# TFT_Touch.net
KiCad netlist of a schematic drawn in EAGLE
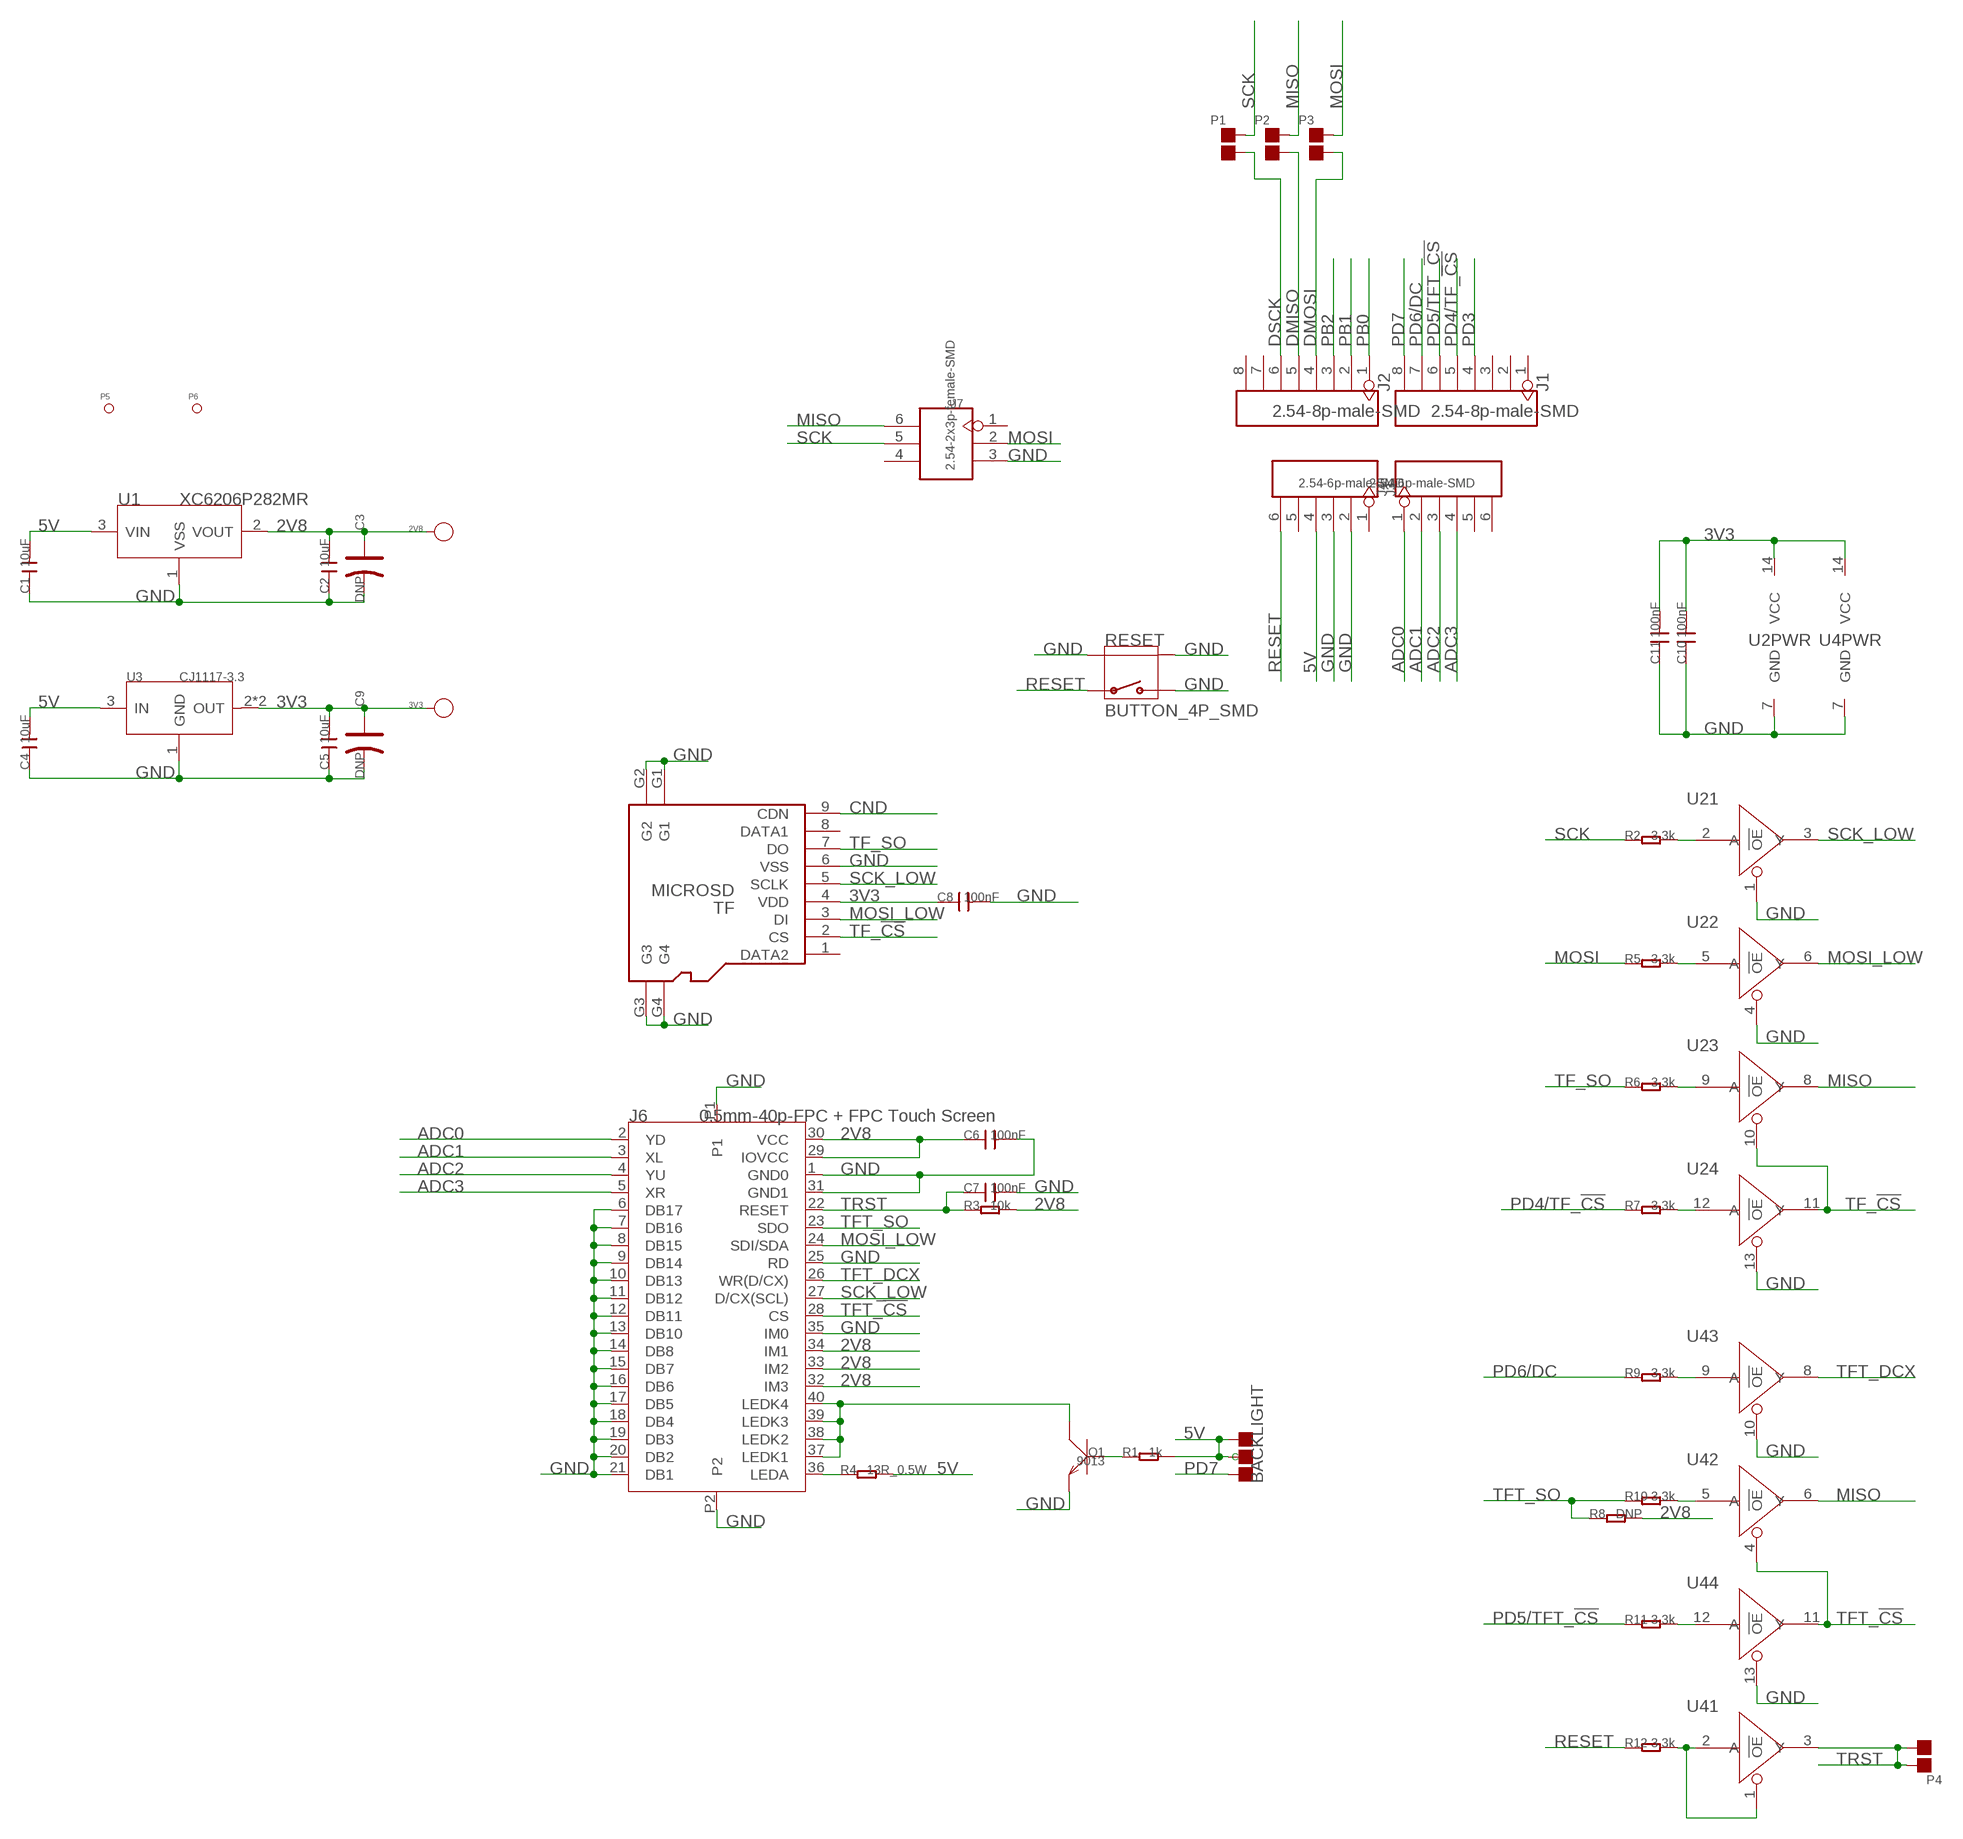
[diagram p0: schematic, sheet 1]

(export (version "E")
  (design (tool "Eeschema 10.0.6"))
  (components
    (comp (ref "2V8")
      (value "PAD-TEST-POINT-CIRCLE'4545'")
      (footprint "eagle-import:TP_4545")
      (fields (field (name "PARTNO") "DNP"))
      (libsource (lib "eagle-import") (part "PAD-TEST-POINT-CIRCLE'4545'"))
    )
    (comp (ref "3V3")
      (value "PAD-TEST-POINT-CIRCLE'4545'")
      (footprint "eagle-import:TP_4545")
      (fields (field (name "PARTNO") "DNP"))
      (libsource (lib "eagle-import") (part "PAD-TEST-POINT-CIRCLE'4545'"))
    )
    (comp (ref "BACKLIGHT")
      (value "DNP")
      (footprint "eagle-import:3P-SMD-4.1X1.5")
      (libsource (lib "eagle-import") (part "PAD-JUMPER-3P-4040"))
    )
    (comp (ref "C1")
      (value "10uF")
      (footprint "eagle-import:C0805")
      (libsource (lib "eagle-import") (part "C-0805"))
    )
    (comp (ref "C2")
      (value "10uF")
      (footprint "eagle-import:C0805")
      (libsource (lib "eagle-import") (part "C-0805"))
    )
    (comp (ref "C3")
      (value "DNP")
      (footprint "eagle-import:AVX-A")
      (libsource (lib "eagle-import") (part "CAP-AVX-A"))
    )
    (comp (ref "C4")
      (value "10uF")
      (footprint "eagle-import:C0805")
      (libsource (lib "eagle-import") (part "C-0805"))
    )
    (comp (ref "C5")
      (value "10uF")
      (footprint "eagle-import:C0805")
      (libsource (lib "eagle-import") (part "C-0805"))
    )
    (comp (ref "C6")
      (value "100nF")
      (footprint "eagle-import:0603@1")
      (libsource (lib "eagle-import") (part "006-C3540"))
    )
    (comp (ref "C7")
      (value "100nF")
      (footprint "eagle-import:0603@1")
      (libsource (lib "eagle-import") (part "006-C3540"))
    )
    (comp (ref "C8")
      (value "100nF")
      (footprint "eagle-import:0603@1")
      (libsource (lib "eagle-import") (part "006-C3540"))
    )
    (comp (ref "C9")
      (value "DNP")
      (footprint "eagle-import:AVX-A")
      (libsource (lib "eagle-import") (part "CAP-AVX-A"))
    )
    (comp (ref "C10")
      (value "100nF")
      (footprint "eagle-import:0603@1")
      (libsource (lib "eagle-import") (part "006-C3540"))
    )
    (comp (ref "C11")
      (value "100nF")
      (footprint "eagle-import:0603@1")
      (libsource (lib "eagle-import") (part "006-C3540"))
    )
    (comp (ref "J1")
      (value "2.54-8p-male-SMD")
      (footprint "eagle-import:8P-2.54-SMD")
      (libsource (lib "eagle-import") (part "HEADER-8P-2.54-SMD"))
    )
    (comp (ref "J2")
      (value "2.54-8p-male-SMD")
      (footprint "eagle-import:8P-2.54-SMD")
      (libsource (lib "eagle-import") (part "HEADER-8P-2.54-SMD"))
    )
    (comp (ref "J3")
      (value "2.54-6p-male-SMD")
      (footprint "eagle-import:6P-2.54-SMD")
      (libsource (lib "eagle-import") (part "HEADER-6P-SMD"))
    )
    (comp (ref "J4")
      (value "2.54-6p-male-SMD")
      (footprint "eagle-import:6P-2.54-SMD")
      (libsource (lib "eagle-import") (part "HEADER-6P-SMD"))
    )
    (comp (ref "J6")
      (value "0.5mm-40p-FPC + FPC Touch Screen")
      (footprint "eagle-import:2.8TFT_FFC")
      (libsource (lib "eagle-import") (part "2.8TFT_FPC"))
    )
    (comp (ref "J7")
      (value "2.54-2x3p-female-SMD")
      (footprint "eagle-import:2X3P-2.54-SMD")
      (libsource (lib "eagle-import") (part "HEADER-2X3P-SMD"))
    )
    (comp (ref "P1")
      (value "PAD-JUMPER-2P")
      (footprint "eagle-import:2P-SMD-1.78X1.27")
      (fields (field (name "PARTNO") "DNP"))
      (libsource (lib "eagle-import") (part "PAD-JUMPER-2P"))
    )
    (comp (ref "P2")
      (value "PAD-JUMPER-2P")
      (footprint "eagle-import:2P-SMD-1.78X1.27")
      (fields (field (name "PARTNO") "DNP"))
      (libsource (lib "eagle-import") (part "PAD-JUMPER-2P"))
    )
    (comp (ref "P3")
      (value "PAD-JUMPER-2P")
      (footprint "eagle-import:2P-SMD-1.78X1.27")
      (fields (field (name "PARTNO") "DNP"))
      (libsource (lib "eagle-import") (part "PAD-JUMPER-2P"))
    )
    (comp (ref "P4")
      (value "PAD-JUMPER-2P")
      (footprint "eagle-import:2P-SMD-1.78X1.27")
      (fields (field (name "PARTNO") "DNP"))
      (libsource (lib "eagle-import") (part "PAD-JUMPER-2P"))
    )
    (comp (ref "P5")
      (value "PAD-MARK")
      (footprint "eagle-import:ROUND-MARK-1.0")
      (fields (field (name "PARTNO") "DNP"))
      (libsource (lib "eagle-import") (part "PAD-MARK"))
    )
    (comp (ref "P6")
      (value "PAD-MARK")
      (footprint "eagle-import:ROUND-MARK-1.0")
      (fields (field (name "PARTNO") "DNP"))
      (libsource (lib "eagle-import") (part "PAD-MARK"))
    )
    (comp (ref "Q1")
      (value "9013")
      (footprint "eagle-import:SOT23")
      (libsource (lib "eagle-import") (part "TRANSISTOR-NPN-SOT23"))
    )
    (comp (ref "R1")
      (value "1k")
      (footprint "eagle-import:R0603")
      (libsource (lib "eagle-import") (part "R-0603"))
    )
    (comp (ref "R2")
      (value "3.3k")
      (footprint "eagle-import:R0603")
      (libsource (lib "eagle-import") (part "R-0603"))
    )
    (comp (ref "R3")
      (value "10k")
      (footprint "eagle-import:R0603")
      (libsource (lib "eagle-import") (part "R-0603"))
    )
    (comp (ref "R4")
      (value "13R_0.5W")
      (footprint "eagle-import:R1206")
      (libsource (lib "eagle-import") (part "R-1206"))
    )
    (comp (ref "R5")
      (value "3.3k")
      (footprint "eagle-import:R0603")
      (libsource (lib "eagle-import") (part "R-0603"))
    )
    (comp (ref "R6")
      (value "3.3k")
      (footprint "eagle-import:R0603")
      (libsource (lib "eagle-import") (part "R-0603"))
    )
    (comp (ref "R7")
      (value "3.3k")
      (footprint "eagle-import:R0603")
      (libsource (lib "eagle-import") (part "R-0603"))
    )
    (comp (ref "R8")
      (value "DNP")
      (footprint "eagle-import:R0603")
      (libsource (lib "eagle-import") (part "R-0603"))
    )
    (comp (ref "R9")
      (value "3.3k")
      (footprint "eagle-import:R0603")
      (libsource (lib "eagle-import") (part "R-0603"))
    )
    (comp (ref "R10")
      (value "3.3k")
      (footprint "eagle-import:R0603")
      (libsource (lib "eagle-import") (part "R-0603"))
    )
    (comp (ref "R11")
      (value "3.3k")
      (footprint "eagle-import:R0603")
      (libsource (lib "eagle-import") (part "R-0603"))
    )
    (comp (ref "R12")
      (value "3.3k")
      (footprint "eagle-import:R0603")
      (libsource (lib "eagle-import") (part "R-0603"))
    )
    (comp (ref "RESET")
      (value "BUTTON_4P_SMD")
      (footprint "eagle-import:4P-SMD-7X3.5X3.5")
      (libsource (lib "eagle-import") (part "BUTTON_4P_SMD"))
    )
    (comp (ref "TF")
      (value "MICROSD")
      (footprint "eagle-import:MICROSD")
      (libsource (lib "eagle-import") (part "MICROSD"))
    )
    (comp (ref "U1")
      (value "XC6206P282MR")
      (footprint "eagle-import:SOT23")
      (libsource (lib "eagle-import") (part "XC6206MR"))
    )
    (comp (ref "U2")
      (value "74VHC125PW")
      (footprint "eagle-import:TSSOP14")
      (libsource (lib "eagle-import") (part "74V125PWHC"))
    )
    (comp (ref "U3")
      (value "CJ1117-3.3")
      (footprint "eagle-import:SOT-223")
      (libsource (lib "eagle-import") (part "LD1117S"))
    )
    (comp (ref "U4")
      (value "74VHC125PW")
      (footprint "eagle-import:TSSOP14")
      (libsource (lib "eagle-import") (part "74V125PWHC"))
    )
  )
  (nets
    (net (code "1") (name "/2V8") (class "Default")
      (node (ref "2V8") (pin "T") (pinfunction "T_T") (pintype "bidirectional"))
      (node (ref "C2") (pin "2") (pinfunction "2_2") (pintype "passive"))
      (node (ref "C3") (pin "+") (pinfunction "+_+") (pintype "passive"))
      (node (ref "C6") (pin "1") (pinfunction "1_1") (pintype "passive"))
      (node (ref "J6") (pin "29") (pinfunction "IOVCC_29") (pintype "bidirectional"))
      (node (ref "J6") (pin "30") (pinfunction "VCC_30") (pintype "bidirectional"))
      (node (ref "J6") (pin "32") (pinfunction "IM3_32") (pintype "bidirectional"))
      (node (ref "J6") (pin "33") (pinfunction "IM2_33") (pintype "bidirectional"))
      (node (ref "J6") (pin "34") (pinfunction "IM1_34") (pintype "bidirectional"))
      (node (ref "R3") (pin "2") (pinfunction "2_2") (pintype "passive"))
      (node (ref "R8") (pin "2") (pinfunction "2_2") (pintype "passive"))
      (node (ref "U1") (pin "2") (pinfunction "VOUT_2") (pintype "output"))
    )
    (net (code "2") (name "/3V3") (class "Default")
      (node (ref "3V3") (pin "T") (pinfunction "T_T") (pintype "bidirectional"))
      (node (ref "C10") (pin "2") (pinfunction "2_2") (pintype "passive"))
      (node (ref "C11") (pin "2") (pinfunction "2_2") (pintype "passive"))
      (node (ref "C5") (pin "2") (pinfunction "2_2") (pintype "passive"))
      (node (ref "C8") (pin "1") (pinfunction "1_1") (pintype "passive"))
      (node (ref "C9") (pin "+") (pinfunction "+_+") (pintype "passive"))
      (node (ref "TF") (pin "4") (pinfunction "VDD_4") (pintype "bidirectional"))
      (node (ref "U2") (pin "14") (pinfunction "VCC_14") (pintype "power_in"))
      (node (ref "U3") (pin "2") (pinfunction "OUT_2") (pintype "bidirectional"))
      (node (ref "U3") (pin "TER") (pinfunction "OUT_TER") (pintype "bidirectional"))
      (node (ref "U4") (pin "14") (pinfunction "VCC_14") (pintype "power_in"))
    )
    (net (code "3") (name "/5V") (class "Default")
      (node (ref "BACKLIGHT") (pin "00") (pinfunction "L_00") (pintype "bidirectional"))
      (node (ref "BACKLIGHT") (pin "MM") (pinfunction "C_MM") (pintype "bidirectional"))
      (node (ref "C1") (pin "2") (pinfunction "2_2") (pintype "passive"))
      (node (ref "C4") (pin "2") (pinfunction "2_2") (pintype "passive"))
      (node (ref "J4") (pin "4") (pinfunction "4_4") (pintype "bidirectional"))
      (node (ref "R1") (pin "2") (pinfunction "2_2") (pintype "passive"))
      (node (ref "R4") (pin "2") (pinfunction "2_2") (pintype "passive"))
      (node (ref "U1") (pin "3") (pinfunction "VIN_3") (pintype "input"))
      (node (ref "U3") (pin "3") (pinfunction "IN_3") (pintype "bidirectional"))
    )
    (net (code "4") (name "/ADC0") (class "Default")
      (node (ref "J3") (pin "1") (pinfunction "1_1") (pintype "bidirectional"))
      (node (ref "J6") (pin "2") (pinfunction "YD_2") (pintype "bidirectional"))
    )
    (net (code "5") (name "/ADC1") (class "Default")
      (node (ref "J3") (pin "2") (pinfunction "2_2") (pintype "bidirectional"))
      (node (ref "J6") (pin "3") (pinfunction "XL_3") (pintype "bidirectional"))
    )
    (net (code "6") (name "/ADC2") (class "Default")
      (node (ref "J3") (pin "3") (pinfunction "3_3") (pintype "bidirectional"))
      (node (ref "J6") (pin "4") (pinfunction "YU_4") (pintype "bidirectional"))
    )
    (net (code "7") (name "/ADC3") (class "Default")
      (node (ref "J3") (pin "4") (pinfunction "4_4") (pintype "bidirectional"))
      (node (ref "J6") (pin "5") (pinfunction "XR_5") (pintype "bidirectional"))
    )
    (net (code "8") (name "/CND") (class "Default")
      (node (ref "TF") (pin "9") (pinfunction "CDN_9") (pintype "bidirectional"))
    )
    (net (code "9") (name "/DMISO") (class "Default")
      (node (ref "J2") (pin "5") (pinfunction "5_5") (pintype "bidirectional"))
      (node (ref "P2") (pin "1") (pinfunction "1_1") (pintype "bidirectional"))
    )
    (net (code "10") (name "/DMOSI") (class "Default")
      (node (ref "J2") (pin "4") (pinfunction "4_4") (pintype "bidirectional"))
      (node (ref "P3") (pin "1") (pinfunction "1_1") (pintype "bidirectional"))
    )
    (net (code "11") (name "/DSCK") (class "Default")
      (node (ref "J2") (pin "6") (pinfunction "6_6") (pintype "bidirectional"))
      (node (ref "P1") (pin "1") (pinfunction "1_1") (pintype "bidirectional"))
    )
    (net (code "12") (name "/GND") (class "Default")
      (node (ref "C1") (pin "1") (pinfunction "1_1") (pintype "passive"))
      (node (ref "C10") (pin "1") (pinfunction "1_1") (pintype "passive"))
      (node (ref "C11") (pin "1") (pinfunction "1_1") (pintype "passive"))
      (node (ref "C2") (pin "1") (pinfunction "1_1") (pintype "passive"))
      (node (ref "C3") (pin "-") (pinfunction "-_-") (pintype "passive"))
      (node (ref "C4") (pin "1") (pinfunction "1_1") (pintype "passive"))
      (node (ref "C5") (pin "1") (pinfunction "1_1") (pintype "passive"))
      (node (ref "C6") (pin "2") (pinfunction "2_2") (pintype "passive"))
      (node (ref "C7") (pin "2") (pinfunction "2_2") (pintype "passive"))
      (node (ref "C8") (pin "2") (pinfunction "2_2") (pintype "passive"))
      (node (ref "C9") (pin "-") (pinfunction "-_-") (pintype "passive"))
      (node (ref "J4") (pin "2") (pinfunction "2_2") (pintype "bidirectional"))
      (node (ref "J4") (pin "3") (pinfunction "3_3") (pintype "bidirectional"))
      (node (ref "J6") (pin "1") (pinfunction "GND0_1") (pintype "bidirectional"))
      (node (ref "J6") (pin "10") (pinfunction "DB13_10") (pintype "bidirectional"))
      (node (ref "J6") (pin "11") (pinfunction "DB12_11") (pintype "bidirectional"))
      (node (ref "J6") (pin "12") (pinfunction "DB11_12") (pintype "bidirectional"))
      (node (ref "J6") (pin "13") (pinfunction "DB10_13") (pintype "bidirectional"))
      (node (ref "J6") (pin "14") (pinfunction "DB8_14") (pintype "bidirectional"))
      (node (ref "J6") (pin "15") (pinfunction "DB7_15") (pintype "bidirectional"))
      (node (ref "J6") (pin "16") (pinfunction "DB6_16") (pintype "bidirectional"))
      (node (ref "J6") (pin "17") (pinfunction "DB5_17") (pintype "bidirectional"))
      (node (ref "J6") (pin "18") (pinfunction "DB4_18") (pintype "bidirectional"))
      (node (ref "J6") (pin "19") (pinfunction "DB3_19") (pintype "bidirectional"))
      (node (ref "J6") (pin "20") (pinfunction "DB2_20") (pintype "bidirectional"))
      (node (ref "J6") (pin "21") (pinfunction "DB1_21") (pintype "bidirectional"))
      (node (ref "J6") (pin "25") (pinfunction "RD_25") (pintype "bidirectional"))
      (node (ref "J6") (pin "31") (pinfunction "GND1_31") (pintype "bidirectional"))
      (node (ref "J6") (pin "35") (pinfunction "IM0_35") (pintype "bidirectional"))
      (node (ref "J6") (pin "6") (pinfunction "DB17_6") (pintype "bidirectional"))
      (node (ref "J6") (pin "7") (pinfunction "DB16_7") (pintype "bidirectional"))
      (node (ref "J6") (pin "8") (pinfunction "DB15_8") (pintype "bidirectional"))
      (node (ref "J6") (pin "9") (pinfunction "DB14_9") (pintype "bidirectional"))
      (node (ref "J6") (pin "P1") (pinfunction "P1_P1") (pintype "bidirectional"))
      (node (ref "J6") (pin "P2") (pinfunction "P2_P2") (pintype "bidirectional"))
      (node (ref "J7") (pin "3") (pinfunction "3_3") (pintype "bidirectional"))
      (node (ref "Q1") (pin "2") (pinfunction "E_2") (pintype "passive"))
      (node (ref "RESET") (pin "2") (pinfunction "2_2") (pintype "bidirectional"))
      (node (ref "RESET") (pin "S1") (pinfunction "S1_S1") (pintype "bidirectional"))
      (node (ref "RESET") (pin "S2") (pinfunction "S2_S2") (pintype "bidirectional"))
      (node (ref "TF") (pin "6") (pinfunction "VSS_6") (pintype "bidirectional"))
      (node (ref "TF") (pin "G1") (pinfunction "G1_G1") (pintype "bidirectional"))
      (node (ref "TF") (pin "G2") (pinfunction "G2_G2") (pintype "bidirectional"))
      (node (ref "TF") (pin "G3") (pinfunction "G3_G3") (pintype "bidirectional"))
      (node (ref "TF") (pin "G4") (pinfunction "G4_G4") (pintype "bidirectional"))
      (node (ref "U1") (pin "1") (pinfunction "VSS_1") (pintype "power_in"))
      (node (ref "U2") (pin "1") (pinfunction "~{OE}_1") (pintype "bidirectional"))
      (node (ref "U2") (pin "13") (pinfunction "~{OE}_13") (pintype "bidirectional"))
      (node (ref "U2") (pin "4") (pinfunction "~{OE}_4") (pintype "bidirectional"))
      (node (ref "U2") (pin "7") (pinfunction "GND_7") (pintype "power_in"))
      (node (ref "U3") (pin "1") (pinfunction "GND_1") (pintype "bidirectional"))
      (node (ref "U4") (pin "10") (pinfunction "~{OE}_10") (pintype "bidirectional"))
      (node (ref "U4") (pin "13") (pinfunction "~{OE}_13") (pintype "bidirectional"))
      (node (ref "U4") (pin "7") (pinfunction "GND_7") (pintype "power_in"))
    )
    (net (code "13") (name "/MISO") (class "Default")
      (node (ref "J7") (pin "6") (pinfunction "6_6") (pintype "bidirectional"))
      (node (ref "P2") (pin "2") (pinfunction "2_2") (pintype "bidirectional"))
      (node (ref "U2") (pin "8") (pinfunction "Y_8") (pintype "bidirectional"))
      (node (ref "U4") (pin "6") (pinfunction "Y_6") (pintype "bidirectional"))
    )
    (net (code "14") (name "/MOSI") (class "Default")
      (node (ref "J7") (pin "2") (pinfunction "2_2") (pintype "bidirectional"))
      (node (ref "P3") (pin "2") (pinfunction "2_2") (pintype "bidirectional"))
      (node (ref "R5") (pin "1") (pinfunction "1_1") (pintype "passive"))
    )
    (net (code "15") (name "/MOSI_LOW") (class "Default")
      (node (ref "J6") (pin "24") (pinfunction "SDI/SDA_24") (pintype "bidirectional"))
      (node (ref "TF") (pin "3") (pinfunction "DI_3") (pintype "bidirectional"))
      (node (ref "U2") (pin "6") (pinfunction "Y_6") (pintype "bidirectional"))
    )
    (net (code "16") (name "/PB0") (class "Default")
      (node (ref "J2") (pin "1") (pinfunction "1_1") (pintype "bidirectional"))
    )
    (net (code "17") (name "/PB1") (class "Default")
      (node (ref "J2") (pin "2") (pinfunction "2_2") (pintype "bidirectional"))
    )
    (net (code "18") (name "/PB2") (class "Default")
      (node (ref "J2") (pin "3") (pinfunction "3_3") (pintype "bidirectional"))
    )
    (net (code "19") (name "/PD3") (class "Default")
      (node (ref "J1") (pin "4") (pinfunction "4_4") (pintype "bidirectional"))
    )
    (net (code "20") (name "/PD4{slash}TF_~{CS}") (class "Default")
      (node (ref "J1") (pin "5") (pinfunction "5_5") (pintype "bidirectional"))
      (node (ref "R7") (pin "1") (pinfunction "1_1") (pintype "passive"))
    )
    (net (code "21") (name "/PD5{slash}TFT_~{CS}") (class "Default")
      (node (ref "J1") (pin "6") (pinfunction "6_6") (pintype "bidirectional"))
      (node (ref "R11") (pin "1") (pinfunction "1_1") (pintype "passive"))
    )
    (net (code "22") (name "/PD6{slash}DC") (class "Default")
      (node (ref "J1") (pin "7") (pinfunction "7_7") (pintype "bidirectional"))
      (node (ref "R9") (pin "1") (pinfunction "1_1") (pintype "passive"))
    )
    (net (code "23") (name "/PD7") (class "Default")
      (node (ref "BACKLIGHT") (pin "11") (pinfunction "R_11") (pintype "bidirectional"))
      (node (ref "J1") (pin "8") (pinfunction "8_8") (pintype "bidirectional"))
    )
    (net (code "24") (name "/RESET") (class "Default")
      (node (ref "J4") (pin "6") (pinfunction "6_6") (pintype "bidirectional"))
      (node (ref "R12") (pin "1") (pinfunction "1_1") (pintype "passive"))
      (node (ref "RESET") (pin "1") (pinfunction "1_1") (pintype "bidirectional"))
    )
    (net (code "25") (name "/SCK") (class "Default")
      (node (ref "J7") (pin "5") (pinfunction "5_5") (pintype "bidirectional"))
      (node (ref "P1") (pin "2") (pinfunction "2_2") (pintype "bidirectional"))
      (node (ref "R2") (pin "1") (pinfunction "1_1") (pintype "passive"))
    )
    (net (code "26") (name "/SCK_LOW") (class "Default")
      (node (ref "J6") (pin "27") (pinfunction "D/CX(SCL)_27") (pintype "bidirectional"))
      (node (ref "TF") (pin "5") (pinfunction "SCLK_5") (pintype "bidirectional"))
      (node (ref "U2") (pin "3") (pinfunction "Y_3") (pintype "bidirectional"))
    )
    (net (code "27") (name "/TFT_DCX") (class "Default")
      (node (ref "J6") (pin "26") (pinfunction "WR(D/CX)_26") (pintype "bidirectional"))
      (node (ref "U4") (pin "8") (pinfunction "Y_8") (pintype "bidirectional"))
    )
    (net (code "28") (name "/TFT_SO") (class "Default")
      (node (ref "J6") (pin "23") (pinfunction "SDO_23") (pintype "bidirectional"))
      (node (ref "R10") (pin "1") (pinfunction "1_1") (pintype "passive"))
      (node (ref "R8") (pin "1") (pinfunction "1_1") (pintype "passive"))
    )
    (net (code "29") (name "/TFT_~{CS}") (class "Default")
      (node (ref "J6") (pin "28") (pinfunction "CS_28") (pintype "bidirectional"))
      (node (ref "U4") (pin "11") (pinfunction "Y_11") (pintype "bidirectional"))
      (node (ref "U4") (pin "4") (pinfunction "~{OE}_4") (pintype "bidirectional"))
    )
    (net (code "30") (name "/TF_SO") (class "Default")
      (node (ref "R6") (pin "1") (pinfunction "1_1") (pintype "passive"))
      (node (ref "TF") (pin "7") (pinfunction "DO_7") (pintype "bidirectional"))
    )
    (net (code "31") (name "/TF_~{CS}") (class "Default")
      (node (ref "TF") (pin "2") (pinfunction "CS_2") (pintype "bidirectional"))
      (node (ref "U2") (pin "10") (pinfunction "~{OE}_10") (pintype "bidirectional"))
      (node (ref "U2") (pin "11") (pinfunction "Y_11") (pintype "bidirectional"))
    )
    (net (code "32") (name "/TRST") (class "Default")
      (node (ref "C7") (pin "1") (pinfunction "1_1") (pintype "passive"))
      (node (ref "J6") (pin "22") (pinfunction "RESET_22") (pintype "bidirectional"))
      (node (ref "P4") (pin "1") (pinfunction "1_1") (pintype "bidirectional"))
      (node (ref "P4") (pin "2") (pinfunction "2_2") (pintype "bidirectional"))
      (node (ref "R3") (pin "1") (pinfunction "1_1") (pintype "passive"))
      (node (ref "U4") (pin "3") (pinfunction "Y_3") (pintype "bidirectional"))
    )
    (net (code "33") (name "Net-(J6-LEDA)") (class "Default")
      (node (ref "J6") (pin "36") (pinfunction "LEDA_36") (pintype "bidirectional"))
      (node (ref "R4") (pin "1") (pinfunction "1_1") (pintype "passive"))
    )
    (net (code "34") (name "Net-(J6-LEDK1)") (class "Default")
      (node (ref "J6") (pin "37") (pinfunction "LEDK1_37") (pintype "bidirectional"))
      (node (ref "J6") (pin "38") (pinfunction "LEDK2_38") (pintype "bidirectional"))
      (node (ref "J6") (pin "39") (pinfunction "LEDK3_39") (pintype "bidirectional"))
      (node (ref "J6") (pin "40") (pinfunction "LEDK4_40") (pintype "bidirectional"))
      (node (ref "Q1") (pin "3") (pinfunction "C_3") (pintype "passive"))
    )
    (net (code "35") (name "Net-(Q1-B)") (class "Default")
      (node (ref "Q1") (pin "1") (pinfunction "B_1") (pintype "passive"))
      (node (ref "R1") (pin "1") (pinfunction "1_1") (pintype "passive"))
    )
    (net (code "36") (name "Net-(U2A-A)") (class "Default")
      (node (ref "R2") (pin "2") (pinfunction "2_2") (pintype "passive"))
      (node (ref "U2") (pin "2") (pinfunction "A_2") (pintype "bidirectional"))
    )
    (net (code "37") (name "Net-(U2B-A)") (class "Default")
      (node (ref "R5") (pin "2") (pinfunction "2_2") (pintype "passive"))
      (node (ref "U2") (pin "5") (pinfunction "A_5") (pintype "bidirectional"))
    )
    (net (code "38") (name "Net-(U2C-A)") (class "Default")
      (node (ref "R6") (pin "2") (pinfunction "2_2") (pintype "passive"))
      (node (ref "U2") (pin "9") (pinfunction "A_9") (pintype "bidirectional"))
    )
    (net (code "39") (name "Net-(U2D-A)") (class "Default")
      (node (ref "R7") (pin "2") (pinfunction "2_2") (pintype "passive"))
      (node (ref "U2") (pin "12") (pinfunction "A_12") (pintype "bidirectional"))
    )
    (net (code "40") (name "Net-(U4A-A)") (class "Default")
      (node (ref "R12") (pin "2") (pinfunction "2_2") (pintype "passive"))
      (node (ref "U4") (pin "1") (pinfunction "~{OE}_1") (pintype "bidirectional"))
      (node (ref "U4") (pin "2") (pinfunction "A_2") (pintype "bidirectional"))
    )
    (net (code "41") (name "Net-(U4B-A)") (class "Default")
      (node (ref "R10") (pin "2") (pinfunction "2_2") (pintype "passive"))
      (node (ref "U4") (pin "5") (pinfunction "A_5") (pintype "bidirectional"))
    )
    (net (code "42") (name "Net-(U4C-A)") (class "Default")
      (node (ref "R9") (pin "2") (pinfunction "2_2") (pintype "passive"))
      (node (ref "U4") (pin "9") (pinfunction "A_9") (pintype "bidirectional"))
    )
    (net (code "43") (name "Net-(U4D-A)") (class "Default")
      (node (ref "R11") (pin "2") (pinfunction "2_2") (pintype "passive"))
      (node (ref "U4") (pin "12") (pinfunction "A_12") (pintype "bidirectional"))
    )
    (net (code "44") (name "unconnected-(J1-Pad1)") (class "Default")
      (node (ref "J1") (pin "1") (pinfunction "1_1") (pintype "bidirectional"))
    )
    (net (code "45") (name "unconnected-(J1-Pad2)") (class "Default")
      (node (ref "J1") (pin "2") (pinfunction "2_2") (pintype "bidirectional"))
    )
    (net (code "46") (name "unconnected-(J1-Pad3)") (class "Default")
      (node (ref "J1") (pin "3") (pinfunction "3_3") (pintype "bidirectional"))
    )
    (net (code "47") (name "unconnected-(J2-Pad7)") (class "Default")
      (node (ref "J2") (pin "7") (pinfunction "7_7") (pintype "bidirectional"))
    )
    (net (code "48") (name "unconnected-(J2-Pad8)") (class "Default")
      (node (ref "J2") (pin "8") (pinfunction "8_8") (pintype "bidirectional"))
    )
    (net (code "49") (name "unconnected-(J3-Pad5)") (class "Default")
      (node (ref "J3") (pin "5") (pinfunction "5_5") (pintype "bidirectional"))
    )
    (net (code "50") (name "unconnected-(J3-Pad6)") (class "Default")
      (node (ref "J3") (pin "6") (pinfunction "6_6") (pintype "bidirectional"))
    )
    (net (code "51") (name "unconnected-(J4-Pad1)") (class "Default")
      (node (ref "J4") (pin "1") (pinfunction "1_1") (pintype "bidirectional"))
    )
    (net (code "52") (name "unconnected-(J4-Pad5)") (class "Default")
      (node (ref "J4") (pin "5") (pinfunction "5_5") (pintype "bidirectional"))
    )
    (net (code "53") (name "unconnected-(J7-Pad1)") (class "Default")
      (node (ref "J7") (pin "1") (pinfunction "1_1") (pintype "bidirectional"))
    )
    (net (code "54") (name "unconnected-(J7-Pad4)") (class "Default")
      (node (ref "J7") (pin "4") (pinfunction "4_4") (pintype "bidirectional"))
    )
    (net (code "55") (name "unconnected-(TF-DATA1-Pad8)") (class "Default")
      (node (ref "TF") (pin "8") (pinfunction "DATA1_8") (pintype "bidirectional"))
    )
    (net (code "56") (name "unconnected-(TF-DATA2-Pad1)") (class "Default")
      (node (ref "TF") (pin "1") (pinfunction "DATA2_1") (pintype "bidirectional"))
    )
  )
)
